# breakout_v0_5.net
KiCad netlist of a schematic drawn in EAGLE
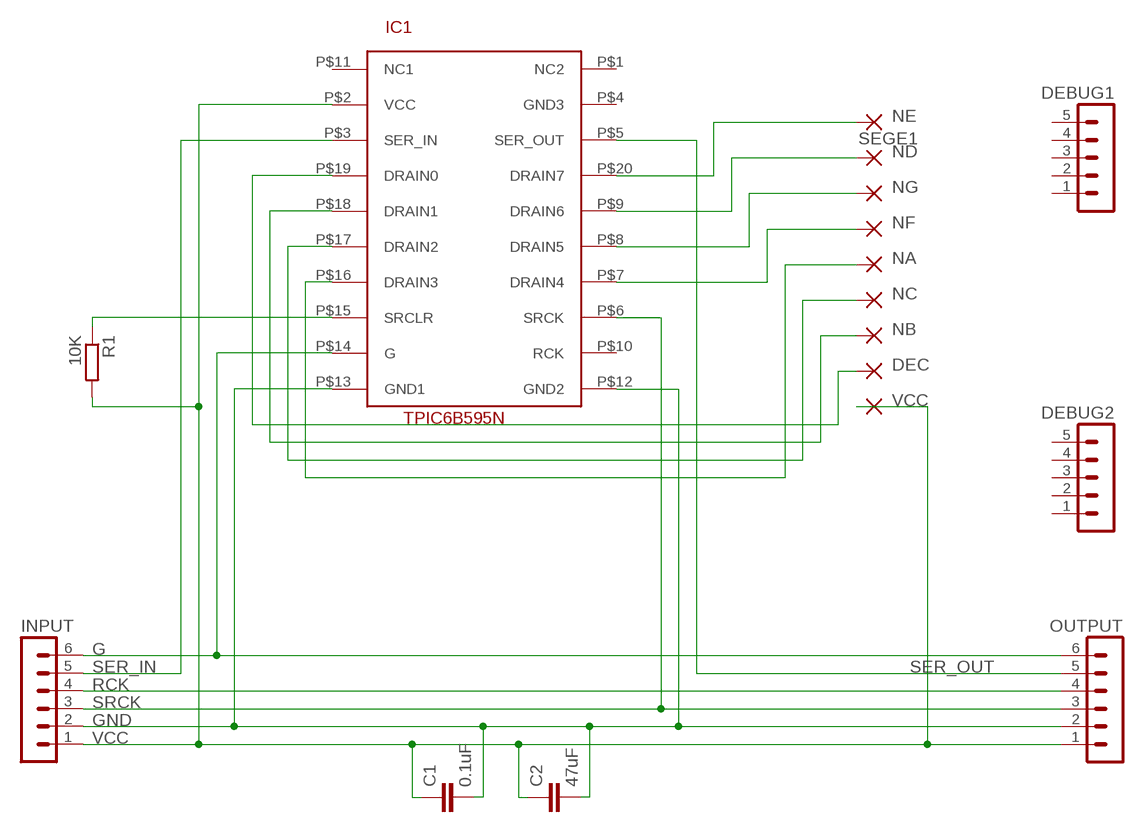
[diagram p0: schematic, sheet 1]

(export (version "E")
  (design (tool "Eeschema 10.0.6"))
  (components
    (comp (ref "C1")
      (value "0.1uF")
      (footprint "eagle-import:RCL_C025-025X050")
      (libsource (lib "eagle-import") (part "RCL_C-EU025-025X050"))
    )
    (comp (ref "C2")
      (value "47uF")
      (footprint "eagle-import:RCL_C025-025X050")
      (libsource (lib "eagle-import") (part "RCL_C-EU025-025X050"))
    )
    (comp (ref "DEBUG1")
      (value "MA05-1")
      (footprint "eagle-import:MA05-1")
      (libsource (lib "eagle-import") (part "MA05-1"))
    )
    (comp (ref "DEBUG2")
      (value "MA05-1")
      (footprint "eagle-import:MA05-1")
      (libsource (lib "eagle-import") (part "MA05-1"))
    )
    (comp (ref "DEC1")
      (value "1,6/0,8")
      (footprint "eagle-import:1,6_0,8")
      (libsource (lib "eagle-import") (part "1,6/0,8"))
    )
    (comp (ref "INPUT")
      (value "CON-LSTB_MA06-1")
      (footprint "eagle-import:CON-LSTB_MA06-1")
      (libsource (lib "eagle-import") (part "CON-LSTB_MA06-1"))
    )
    (comp (ref "OUTPUT")
      (value "CON-LSTB_MA06-1")
      (footprint "eagle-import:CON-LSTB_MA06-1")
      (libsource (lib "eagle-import") (part "CON-LSTB_MA06-1"))
    )
    (comp (ref "R1")
      (value "10K")
      (footprint "eagle-import:RCL_0207_7")
      (libsource (lib "eagle-import") (part "RCL_R-EU_0207/7"))
    )
    (comp (ref "SEGA1")
      (value "1,6/0,8")
      (footprint "eagle-import:1,6_0,8")
      (libsource (lib "eagle-import") (part "1,6/0,8"))
    )
    (comp (ref "SEGB1")
      (value "1,6/0,8")
      (footprint "eagle-import:1,6_0,8")
      (libsource (lib "eagle-import") (part "1,6/0,8"))
    )
    (comp (ref "SEGC1")
      (value "1,6/0,8")
      (footprint "eagle-import:1,6_0,8")
      (libsource (lib "eagle-import") (part "1,6/0,8"))
    )
    (comp (ref "SEGD1")
      (value "1,6/0,8")
      (footprint "eagle-import:1,6_0,8")
      (libsource (lib "eagle-import") (part "1,6/0,8"))
    )
    (comp (ref "SEGE1")
      (value "1,6/0,8")
      (footprint "eagle-import:1,6_0,8")
      (libsource (lib "eagle-import") (part "1,6/0,8"))
    )
    (comp (ref "SEGF1")
      (value "1,6/0,8")
      (footprint "eagle-import:1,6_0,8")
      (libsource (lib "eagle-import") (part "1,6/0,8"))
    )
    (comp (ref "SEGG1")
      (value "1,6/0,8")
      (footprint "eagle-import:1,6_0,8")
      (libsource (lib "eagle-import") (part "1,6/0,8"))
    )
    (comp (ref "U$1")
      (value "TPIC6B595N_TPIC6B595NPDIP-20")
      (footprint "eagle-import:TPIC6B595N_PDIP-20")
      (libsource (lib "eagle-import") (part "TPIC6B595N_TPIC6B595NPDIP-20"))
    )
    (comp (ref "VCC1")
      (value "1,6/0,8")
      (footprint "eagle-import:1,6_0,8")
      (libsource (lib "eagle-import") (part "1,6/0,8"))
    )
  )
  (nets
    (net (code "1") (name "/DEC") (class "Default")
      (node (ref "U$1") (pin "P$19") (pinfunction "DRAIN0_P$19") (pintype "bidirectional"))
      (node (ref "VCC1") (pin "1") (pinfunction "P_1") (pintype "passive"))
    )
    (net (code "2") (name "/G") (class "Default")
      (node (ref "INPUT") (pin "6") (pinfunction "6_6") (pintype "passive"))
      (node (ref "OUTPUT") (pin "6") (pinfunction "6_6") (pintype "passive"))
      (node (ref "U$1") (pin "P$14") (pinfunction "G_P$14") (pintype "bidirectional"))
    )
    (net (code "3") (name "/GND") (class "Default")
      (node (ref "C1") (pin "2") (pinfunction "2_2") (pintype "passive"))
      (node (ref "C2") (pin "2") (pinfunction "2_2") (pintype "passive"))
      (node (ref "INPUT") (pin "2") (pinfunction "2_2") (pintype "passive"))
      (node (ref "OUTPUT") (pin "2") (pinfunction "2_2") (pintype "passive"))
      (node (ref "U$1") (pin "P$12") (pinfunction "GND2_P$12") (pintype "bidirectional"))
      (node (ref "U$1") (pin "P$13") (pinfunction "GND1_P$13") (pintype "bidirectional"))
    )
    (net (code "4") (name "/NA") (class "Default")
      (node (ref "SEGC1") (pin "1") (pinfunction "P_1") (pintype "passive"))
      (node (ref "U$1") (pin "P$16") (pinfunction "DRAIN3_P$16") (pintype "bidirectional"))
    )
    (net (code "5") (name "/NB") (class "Default")
      (node (ref "DEC1") (pin "1") (pinfunction "P_1") (pintype "passive"))
      (node (ref "U$1") (pin "P$18") (pinfunction "DRAIN1_P$18") (pintype "bidirectional"))
    )
    (net (code "6") (name "/NC") (class "Default")
      (node (ref "SEGB1") (pin "1") (pinfunction "P_1") (pintype "passive"))
      (node (ref "U$1") (pin "P$17") (pinfunction "DRAIN2_P$17") (pintype "bidirectional"))
    )
    (net (code "7") (name "/ND") (class "Default")
      (node (ref "SEGG1") (pin "1") (pinfunction "P_1") (pintype "passive"))
      (node (ref "U$1") (pin "P$9") (pinfunction "DRAIN6_P$9") (pintype "bidirectional"))
    )
    (net (code "8") (name "/NE") (class "Default")
      (node (ref "SEGE1") (pin "1") (pinfunction "P_1") (pintype "passive"))
      (node (ref "U$1") (pin "P$20") (pinfunction "DRAIN7_P$20") (pintype "bidirectional"))
    )
    (net (code "9") (name "/NF") (class "Default")
      (node (ref "SEGA1") (pin "1") (pinfunction "P_1") (pintype "passive"))
      (node (ref "U$1") (pin "P$7") (pinfunction "DRAIN4_P$7") (pintype "bidirectional"))
    )
    (net (code "10") (name "/NG") (class "Default")
      (node (ref "SEGF1") (pin "1") (pinfunction "P_1") (pintype "passive"))
      (node (ref "U$1") (pin "P$8") (pinfunction "DRAIN5_P$8") (pintype "bidirectional"))
    )
    (net (code "11") (name "/RCK") (class "Default")
      (node (ref "INPUT") (pin "4") (pinfunction "4_4") (pintype "passive"))
      (node (ref "OUTPUT") (pin "4") (pinfunction "4_4") (pintype "passive"))
    )
    (net (code "12") (name "/SER_IN") (class "Default")
      (node (ref "INPUT") (pin "5") (pinfunction "5_5") (pintype "passive"))
      (node (ref "U$1") (pin "P$3") (pinfunction "SER_IN_P$3") (pintype "bidirectional"))
    )
    (net (code "13") (name "/SER_OUT") (class "Default")
      (node (ref "OUTPUT") (pin "5") (pinfunction "5_5") (pintype "passive"))
      (node (ref "U$1") (pin "P$5") (pinfunction "SER_OUT_P$5") (pintype "bidirectional"))
    )
    (net (code "14") (name "/SRCK") (class "Default")
      (node (ref "INPUT") (pin "3") (pinfunction "3_3") (pintype "passive"))
      (node (ref "OUTPUT") (pin "3") (pinfunction "3_3") (pintype "passive"))
      (node (ref "U$1") (pin "P$6") (pinfunction "SRCK_P$6") (pintype "bidirectional"))
    )
    (net (code "15") (name "/VCC") (class "Default")
      (node (ref "C1") (pin "1") (pinfunction "1_1") (pintype "passive"))
      (node (ref "C2") (pin "1") (pinfunction "1_1") (pintype "passive"))
      (node (ref "INPUT") (pin "1") (pinfunction "1_1") (pintype "passive"))
      (node (ref "OUTPUT") (pin "1") (pinfunction "1_1") (pintype "passive"))
      (node (ref "R1") (pin "2") (pinfunction "2_2") (pintype "passive"))
      (node (ref "SEGD1") (pin "1") (pinfunction "P_1") (pintype "passive"))
      (node (ref "U$1") (pin "P$2") (pinfunction "VCC_P$2") (pintype "bidirectional"))
    )
    (net (code "16") (name "Net-(U$1-SRCLR)") (class "Default")
      (node (ref "R1") (pin "1") (pinfunction "1_1") (pintype "passive"))
      (node (ref "U$1") (pin "P$15") (pinfunction "SRCLR_P$15") (pintype "bidirectional"))
    )
    (net (code "17") (name "unconnected-(DEBUG1-Pad1)") (class "Default")
      (node (ref "DEBUG1") (pin "1") (pinfunction "1_1") (pintype "passive"))
    )
    (net (code "18") (name "unconnected-(DEBUG1-Pad2)") (class "Default")
      (node (ref "DEBUG1") (pin "2") (pinfunction "2_2") (pintype "passive"))
    )
    (net (code "19") (name "unconnected-(DEBUG1-Pad3)") (class "Default")
      (node (ref "DEBUG1") (pin "3") (pinfunction "3_3") (pintype "passive"))
    )
    (net (code "20") (name "unconnected-(DEBUG1-Pad4)") (class "Default")
      (node (ref "DEBUG1") (pin "4") (pinfunction "4_4") (pintype "passive"))
    )
    (net (code "21") (name "unconnected-(DEBUG1-Pad5)") (class "Default")
      (node (ref "DEBUG1") (pin "5") (pinfunction "5_5") (pintype "passive"))
    )
    (net (code "22") (name "unconnected-(DEBUG2-Pad1)") (class "Default")
      (node (ref "DEBUG2") (pin "1") (pinfunction "1_1") (pintype "passive"))
    )
    (net (code "23") (name "unconnected-(DEBUG2-Pad2)") (class "Default")
      (node (ref "DEBUG2") (pin "2") (pinfunction "2_2") (pintype "passive"))
    )
    (net (code "24") (name "unconnected-(DEBUG2-Pad3)") (class "Default")
      (node (ref "DEBUG2") (pin "3") (pinfunction "3_3") (pintype "passive"))
    )
    (net (code "25") (name "unconnected-(DEBUG2-Pad4)") (class "Default")
      (node (ref "DEBUG2") (pin "4") (pinfunction "4_4") (pintype "passive"))
    )
    (net (code "26") (name "unconnected-(DEBUG2-Pad5)") (class "Default")
      (node (ref "DEBUG2") (pin "5") (pinfunction "5_5") (pintype "passive"))
    )
    (net (code "27") (name "unconnected-(U$1-GND3-PadP$4)") (class "Default")
      (node (ref "U$1") (pin "P$4") (pinfunction "GND3_P$4") (pintype "bidirectional"))
    )
    (net (code "28") (name "unconnected-(U$1-NC1-PadP$11)") (class "Default")
      (node (ref "U$1") (pin "P$11") (pinfunction "NC1_P$11") (pintype "bidirectional"))
    )
    (net (code "29") (name "unconnected-(U$1-NC2-PadP$1)") (class "Default")
      (node (ref "U$1") (pin "P$1") (pinfunction "NC2_P$1") (pintype "bidirectional"))
    )
    (net (code "30") (name "unconnected-(U$1-RCK-PadP$10)") (class "Default")
      (node (ref "U$1") (pin "P$10") (pinfunction "RCK_P$10") (pintype "bidirectional"))
    )
  )
)
